# Buck_Schematic.net
KiCad netlist of a schematic drawn in Altium Designer
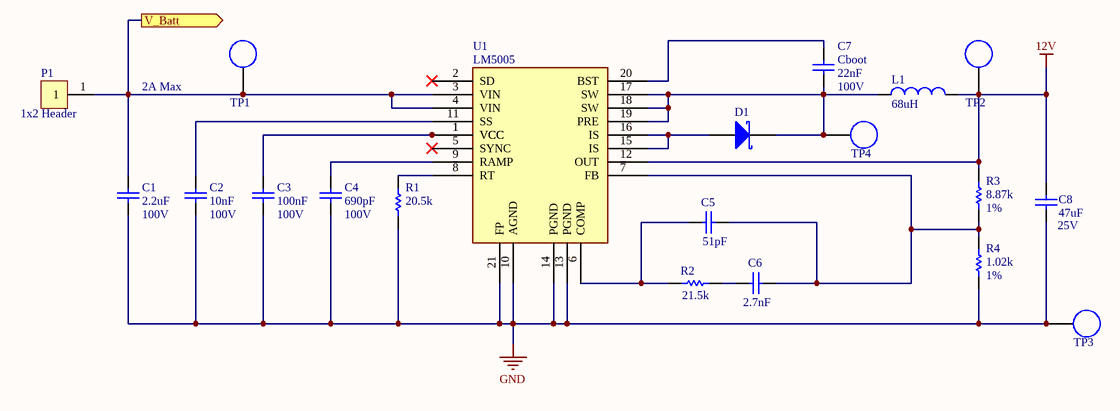
[diagram p0: Buck_Schematic.schdoc]

(export (version "E")
  (design (tool "Eeschema 10.0.6"))
  (components
    (comp (ref "C1")
      (value "2.2uF")
      (footprint "1210 - Capacitor")
      (description "Nonpolarized Capacitor")
      (libsource (lib "General") (part "Capacitor - Nonpolarized"))
    )
    (comp (ref "C2")
      (value "10nF")
      (footprint "0805 - Capacitor")
      (description "Nonpolarized Capacitor")
      (libsource (lib "General") (part "Capacitor - Nonpolarized"))
    )
    (comp (ref "C3")
      (value "100nF")
      (footprint "0805 - Capacitor")
      (description "Nonpolarized Capacitor")
      (libsource (lib "General") (part "Capacitor - Nonpolarized"))
    )
    (comp (ref "C4")
      (value "690pF")
      (footprint "0805 - Capacitor")
      (description "Nonpolarized Capacitor")
      (libsource (lib "General") (part "Capacitor - Nonpolarized"))
    )
    (comp (ref "C5")
      (value "51pF")
      (footprint "0805 - Capacitor")
      (description "Nonpolarized Capacitor")
      (libsource (lib "General") (part "Capacitor - Nonpolarized"))
    )
    (comp (ref "C6")
      (value "2.7nF")
      (footprint "0805 - Capacitor")
      (description "Nonpolarized Capacitor")
      (libsource (lib "General") (part "Capacitor - Nonpolarized"))
    )
    (comp (ref "C7")
      (value "Cboot")
      (footprint "0805 - Capacitor")
      (description "Nonpolarized Capacitor")
      (fields (field (name "ALTIUM_VALUE") "22nF"))
      (libsource (lib "General") (part "Capacitor - Nonpolarized"))
    )
    (comp (ref "C8")
      (value "47uF")
      (footprint "1206 - Capacitor")
      (description "Nonpolarized Capacitor")
      (fields (field (name "Comment") "Capacitor - Nonpolarized"))
      (libsource (lib "General") (part "Capacitor - Nonpolarized"))
    )
    (comp (ref "D1")
      (value "Diode - Schottky")
      (footprint "SMA - DIODE")
      (description "Schottky Rectifier")
      (libsource (lib "General") (part "Diode - Schottky"))
    )
    (comp (ref "L1")
      (value "68uH")
      (footprint "MSS1210 - INDUCTOR")
      (description "Inductor")
      (libsource (lib "General") (part "Inductor"))
    )
    (comp (ref "P1")
      (value "1x2 Header")
      (footprint "74650094R")
      (libsource (lib "GeneralConnectors") (part "74650094R"))
    )
    (comp (ref "R1")
      (value "20.5k")
      (footprint "0603 - Resistor")
      (description "Resistor")
      (libsource (lib "General") (part "Resistor"))
    )
    (comp (ref "R2")
      (value "21.5k")
      (footprint "0603 - Resistor")
      (description "Resistor")
      (libsource (lib "General") (part "Resistor"))
    )
    (comp (ref "R3")
      (value "8.87k")
      (footprint "0805 - Resistor")
      (description "Resistor")
      (libsource (lib "General") (part "Resistor"))
    )
    (comp (ref "R4")
      (value "1.02k")
      (footprint "0805 - Resistor")
      (description "Resistor")
      (libsource (lib "General") (part "Resistor"))
    )
    (comp (ref "TP1")
      (value "Test Point")
      (footprint "Test Point")
      (libsource (lib "General") (part "Test Point"))
    )
    (comp (ref "TP2")
      (value "Test Point")
      (footprint "Test Point")
      (libsource (lib "General") (part "Test Point"))
    )
    (comp (ref "TP3")
      (value "Test Point")
      (footprint "Test Point")
      (libsource (lib "General") (part "Test Point"))
    )
    (comp (ref "TP4")
      (value "Test Point")
      (footprint "Test Point")
      (libsource (lib "General") (part "Test Point"))
    )
    (comp (ref "U1")
      (value "LM5005")
      (footprint "LM5005")
      (description "7V to 75V 2.5A, Buck Converter")
      (fields
        (field (name "MANUFACTURER") "Texas Instruments")
        (field (name "MANUFACTURER PART NUMBER") "LM5005MHX/NOPB")
      )
      (libsource (lib "GeneralComponents") (part "LM5005"))
    )
  )
  (nets
    (net (code "1") (name "/V_Batt") (class "Default")
      (node (ref "C1") (pin "2") (pinfunction "2_2") (pintype "passive"))
      (node (ref "P1") (pin "1") (pinfunction "1_1") (pintype "passive"))
      (node (ref "TP1") (pin "TP?") (pinfunction "0_TP?") (pintype "passive"))
      (node (ref "U1") (pin "3") (pinfunction "VIN_3") (pintype "passive"))
      (node (ref "U1") (pin "4") (pinfunction "VIN_4") (pintype "passive"))
    )
    (net (code "2") (name "12V") (class "Default")
      (node (ref "C8") (pin "2") (pinfunction "2_2") (pintype "passive"))
      (node (ref "L1") (pin "2") (pinfunction "2_2") (pintype "passive"))
      (node (ref "R3") (pin "2") (pinfunction "2_2") (pintype "passive"))
      (node (ref "TP2") (pin "TP?") (pinfunction "0_TP?") (pintype "passive"))
      (node (ref "U1") (pin "12") (pinfunction "OUT_12") (pintype "passive"))
    )
    (net (code "3") (name "GND") (class "Default")
      (node (ref "C1") (pin "1") (pinfunction "1_1") (pintype "passive"))
      (node (ref "C2") (pin "1") (pinfunction "1_1") (pintype "passive"))
      (node (ref "C3") (pin "1") (pinfunction "1_1") (pintype "passive"))
      (node (ref "C4") (pin "1") (pinfunction "1_1") (pintype "passive"))
      (node (ref "C8") (pin "1") (pinfunction "1_1") (pintype "passive"))
      (node (ref "R1") (pin "1") (pinfunction "1_1") (pintype "passive"))
      (node (ref "R4") (pin "1") (pinfunction "1_1") (pintype "passive"))
      (node (ref "TP3") (pin "TP?") (pinfunction "0_TP?") (pintype "passive"))
      (node (ref "U1") (pin "10") (pinfunction "AGND_10") (pintype "passive"))
      (node (ref "U1") (pin "13") (pinfunction "PGND_13") (pintype "passive"))
      (node (ref "U1") (pin "14") (pinfunction "PGND_14") (pintype "passive"))
      (node (ref "U1") (pin "21") (pinfunction "FP_21") (pintype "passive"))
    )
    (net (code "4") (name "Net-(C6-Pad2)") (class "Default")
      (node (ref "C6") (pin "2") (pinfunction "2_2") (pintype "passive"))
      (node (ref "R2") (pin "1") (pinfunction "1_1") (pintype "passive"))
    )
    (net (code "5") (name "Net-(D1-A)") (class "Default")
      (node (ref "D1") (pin "1") (pinfunction "A_1") (pintype "passive"))
      (node (ref "U1") (pin "15") (pinfunction "IS_15") (pintype "passive"))
      (node (ref "U1") (pin "16") (pinfunction "IS_16") (pintype "passive"))
    )
    (net (code "6") (name "Net-(D1-K)") (class "Default")
      (node (ref "C7") (pin "1") (pinfunction "1_1") (pintype "passive"))
      (node (ref "D1") (pin "2") (pinfunction "K_2") (pintype "passive"))
      (node (ref "L1") (pin "1") (pinfunction "1_1") (pintype "passive"))
      (node (ref "TP4") (pin "TP?") (pinfunction "0_TP?") (pintype "passive"))
      (node (ref "U1") (pin "17") (pinfunction "SW_17") (pintype "passive"))
      (node (ref "U1") (pin "18") (pinfunction "SW_18") (pintype "passive"))
      (node (ref "U1") (pin "19") (pinfunction "PRE_19") (pintype "passive"))
    )
    (net (code "7") (name "Net-(U1-BST)") (class "Default")
      (node (ref "C7") (pin "2") (pinfunction "2_2") (pintype "passive"))
      (node (ref "U1") (pin "20") (pinfunction "BST_20") (pintype "passive"))
    )
    (net (code "8") (name "Net-(U1-COMP)") (class "Default")
      (node (ref "C5") (pin "2") (pinfunction "2_2") (pintype "passive"))
      (node (ref "R2") (pin "2") (pinfunction "2_2") (pintype "passive"))
      (node (ref "U1") (pin "6") (pinfunction "COMP_6") (pintype "passive"))
    )
    (net (code "9") (name "Net-(U1-FB)") (class "Default")
      (node (ref "C5") (pin "1") (pinfunction "1_1") (pintype "passive"))
      (node (ref "C6") (pin "1") (pinfunction "1_1") (pintype "passive"))
      (node (ref "R3") (pin "1") (pinfunction "1_1") (pintype "passive"))
      (node (ref "R4") (pin "2") (pinfunction "2_2") (pintype "passive"))
      (node (ref "U1") (pin "7") (pinfunction "FB_7") (pintype "passive"))
    )
    (net (code "10") (name "Net-(U1-RAMP)") (class "Default")
      (node (ref "C4") (pin "2") (pinfunction "2_2") (pintype "passive"))
      (node (ref "U1") (pin "9") (pinfunction "RAMP_9") (pintype "passive"))
    )
    (net (code "11") (name "Net-(U1-RT)") (class "Default")
      (node (ref "R1") (pin "2") (pinfunction "2_2") (pintype "passive"))
      (node (ref "U1") (pin "8") (pinfunction "RT_8") (pintype "passive"))
    )
    (net (code "12") (name "Net-(U1-SS)") (class "Default")
      (node (ref "C2") (pin "2") (pinfunction "2_2") (pintype "passive"))
      (node (ref "U1") (pin "11") (pinfunction "SS_11") (pintype "passive"))
    )
    (net (code "13") (name "Net-(U1-VCC)") (class "Default")
      (node (ref "C3") (pin "2") (pinfunction "2_2") (pintype "passive"))
      (node (ref "U1") (pin "1") (pinfunction "VCC_1") (pintype "passive"))
    )
    (net (code "14") (name "unconnected-(U1-SD-Pad2)") (class "Default")
      (node (ref "U1") (pin "2") (pinfunction "SD_2") (pintype "passive+no_connect"))
    )
    (net (code "15") (name "unconnected-(U1-SYNC-Pad5)") (class "Default")
      (node (ref "U1") (pin "5") (pinfunction "SYNC_5") (pintype "passive+no_connect"))
    )
  )
)
